# USBHostModule.net
KiCad netlist of a schematic drawn in EAGLE
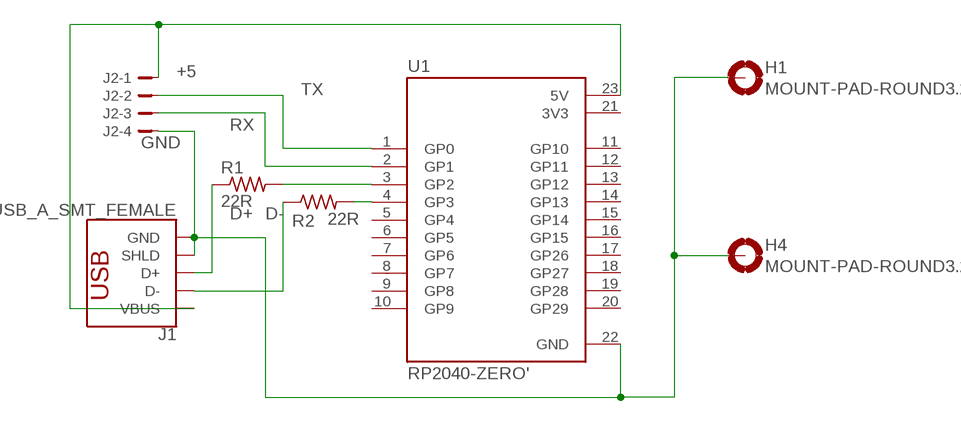
[diagram p0: schematic, sheet 1]

(export (version "E")
  (design (tool "Eeschema 10.0.6"))
  (components
    (comp (ref "H1")
      (value "MOUNT-PAD-ROUND3.2")
      (footprint "eagle-import:3,2-PAD")
      (libsource (lib "eagle-import") (part "MOUNT-PAD-ROUND3.2"))
    )
    (comp (ref "H4")
      (value "MOUNT-PAD-ROUND3.2")
      (footprint "eagle-import:3,2-PAD")
      (libsource (lib "eagle-import") (part "MOUNT-PAD-ROUND3.2"))
    )
    (comp (ref "J1")
      (value "USB_A_SMT_FEMALE")
      (footprint "eagle-import:USB-A-S-SILK-FEMALE")
      (libsource (lib "eagle-import") (part "USB_A_SMT_FEMALE"))
    )
    (comp (ref "J2")
      (value "JST-PH-4_TH-RA")
      (footprint "eagle-import:S4B-PH-KL")
      (fields (field (name "MF") "JST") (field (name "MPN") "S4B-PH-KL"))
      (libsource (lib "eagle-import") (part "JST-PH-4_TH-RA"))
    )
    (comp (ref "R1")
      (value "22R")
      (footprint "eagle-import:R1206")
      (libsource (lib "eagle-import") (part "R-US_R1206"))
    )
    (comp (ref "R2")
      (value "22R")
      (footprint "eagle-import:R1206")
      (libsource (lib "eagle-import") (part "R-US_R1206"))
    )
    (comp (ref "U1")
      (value "RP2040-ZERO'")
      (footprint "eagle-import:MODULE_RP2040-ZERO")
      (fields (field (name "MF") "Waveshare Electronics") (field (name "MP") "RP2040-ZERO"))
      (libsource (lib "eagle-import") (part "RP2040-ZERO'"))
    )
  )
  (nets
    (net (code "1") (name "/+5") (class "Default")
      (node (ref "J1") (pin "VBUS") (pinfunction "VBUS_VBUS") (pintype "power_in"))
      (node (ref "J2") (pin "1") (pinfunction "1_1") (pintype "passive"))
      (node (ref "U1") (pin "23") (pinfunction "5V_23") (pintype "power_in"))
    )
    (net (code "2") (name "/3V3") (class "Default")
      (node (ref "U1") (pin "21") (pinfunction "3V3_21") (pintype "power_in"))
    )
    (net (code "3") (name "/D+") (class "Default")
      (node (ref "J1") (pin "D+") (pinfunction "D+_D+") (pintype "bidirectional"))
      (node (ref "R1") (pin "1") (pinfunction "1_1") (pintype "passive"))
    )
    (net (code "4") (name "/D-") (class "Default")
      (node (ref "J1") (pin "D-") (pinfunction "D-_D-") (pintype "bidirectional"))
      (node (ref "R2") (pin "1") (pinfunction "1_1") (pintype "passive"))
    )
    (net (code "5") (name "/GND") (class "Default")
      (node (ref "H1") (pin "B3,2") (pinfunction "MOUNT_B3,2") (pintype "passive"))
      (node (ref "H4") (pin "B3,2") (pinfunction "MOUNT_B3,2") (pintype "passive"))
      (node (ref "J1") (pin "GND") (pinfunction "GND_GND") (pintype "power_in"))
      (node (ref "J1") (pin "SHLD1") (pinfunction "SHLD_SHLD1") (pintype "bidirectional"))
      (node (ref "J1") (pin "SHLD2") (pinfunction "SHLD_SHLD2") (pintype "bidirectional"))
      (node (ref "J2") (pin "4") (pinfunction "1_4") (pintype "passive"))
      (node (ref "U1") (pin "22") (pinfunction "GND_22") (pintype "power_in"))
    )
    (net (code "6") (name "/RX") (class "Default")
      (node (ref "J2") (pin "3") (pinfunction "1_3") (pintype "passive"))
      (node (ref "U1") (pin "2") (pinfunction "GP1_2") (pintype "bidirectional"))
    )
    (net (code "7") (name "/TX") (class "Default")
      (node (ref "J2") (pin "2") (pinfunction "1_2") (pintype "passive"))
      (node (ref "U1") (pin "1") (pinfunction "GP0_1") (pintype "bidirectional"))
    )
    (net (code "8") (name "Net-(U1-GP2)") (class "Default")
      (node (ref "R1") (pin "2") (pinfunction "2_2") (pintype "passive"))
      (node (ref "U1") (pin "3") (pinfunction "GP2_3") (pintype "bidirectional"))
    )
    (net (code "9") (name "Net-(U1-GP3)") (class "Default")
      (node (ref "R2") (pin "2") (pinfunction "2_2") (pintype "passive"))
      (node (ref "U1") (pin "4") (pinfunction "GP3_4") (pintype "bidirectional"))
    )
    (net (code "10") (name "unconnected-(U1-GP4-Pad5)") (class "Default")
      (node (ref "U1") (pin "5") (pinfunction "GP4_5") (pintype "bidirectional"))
    )
    (net (code "11") (name "unconnected-(U1-GP5-Pad6)") (class "Default")
      (node (ref "U1") (pin "6") (pinfunction "GP5_6") (pintype "bidirectional"))
    )
    (net (code "12") (name "unconnected-(U1-GP6-Pad7)") (class "Default")
      (node (ref "U1") (pin "7") (pinfunction "GP6_7") (pintype "bidirectional"))
    )
    (net (code "13") (name "unconnected-(U1-GP7-Pad8)") (class "Default")
      (node (ref "U1") (pin "8") (pinfunction "GP7_8") (pintype "bidirectional"))
    )
    (net (code "14") (name "unconnected-(U1-GP8-Pad9)") (class "Default")
      (node (ref "U1") (pin "9") (pinfunction "GP8_9") (pintype "bidirectional"))
    )
    (net (code "15") (name "unconnected-(U1-GP9-Pad10)") (class "Default")
      (node (ref "U1") (pin "10") (pinfunction "GP9_10") (pintype "bidirectional"))
    )
    (net (code "16") (name "unconnected-(U1-GP10-Pad11)") (class "Default")
      (node (ref "U1") (pin "11") (pinfunction "GP10_11") (pintype "bidirectional"))
    )
    (net (code "17") (name "unconnected-(U1-GP11-Pad12)") (class "Default")
      (node (ref "U1") (pin "12") (pinfunction "GP11_12") (pintype "bidirectional"))
    )
    (net (code "18") (name "unconnected-(U1-GP12-Pad13)") (class "Default")
      (node (ref "U1") (pin "13") (pinfunction "GP12_13") (pintype "bidirectional"))
    )
    (net (code "19") (name "unconnected-(U1-GP13-Pad14)") (class "Default")
      (node (ref "U1") (pin "14") (pinfunction "GP13_14") (pintype "bidirectional"))
    )
    (net (code "20") (name "unconnected-(U1-GP14-Pad15)") (class "Default")
      (node (ref "U1") (pin "15") (pinfunction "GP14_15") (pintype "bidirectional"))
    )
    (net (code "21") (name "unconnected-(U1-GP15-Pad16)") (class "Default")
      (node (ref "U1") (pin "16") (pinfunction "GP15_16") (pintype "bidirectional"))
    )
    (net (code "22") (name "unconnected-(U1-GP26-Pad17)") (class "Default")
      (node (ref "U1") (pin "17") (pinfunction "GP26_17") (pintype "bidirectional"))
    )
    (net (code "23") (name "unconnected-(U1-GP27-Pad18)") (class "Default")
      (node (ref "U1") (pin "18") (pinfunction "GP27_18") (pintype "bidirectional"))
    )
    (net (code "24") (name "unconnected-(U1-GP28-Pad19)") (class "Default")
      (node (ref "U1") (pin "19") (pinfunction "GP28_19") (pintype "bidirectional"))
    )
    (net (code "25") (name "unconnected-(U1-GP29-Pad20)") (class "Default")
      (node (ref "U1") (pin "20") (pinfunction "GP29_20") (pintype "bidirectional"))
    )
  )
)
